# finalSchematics.net
KiCad netlist of a schematic drawn in EAGLE
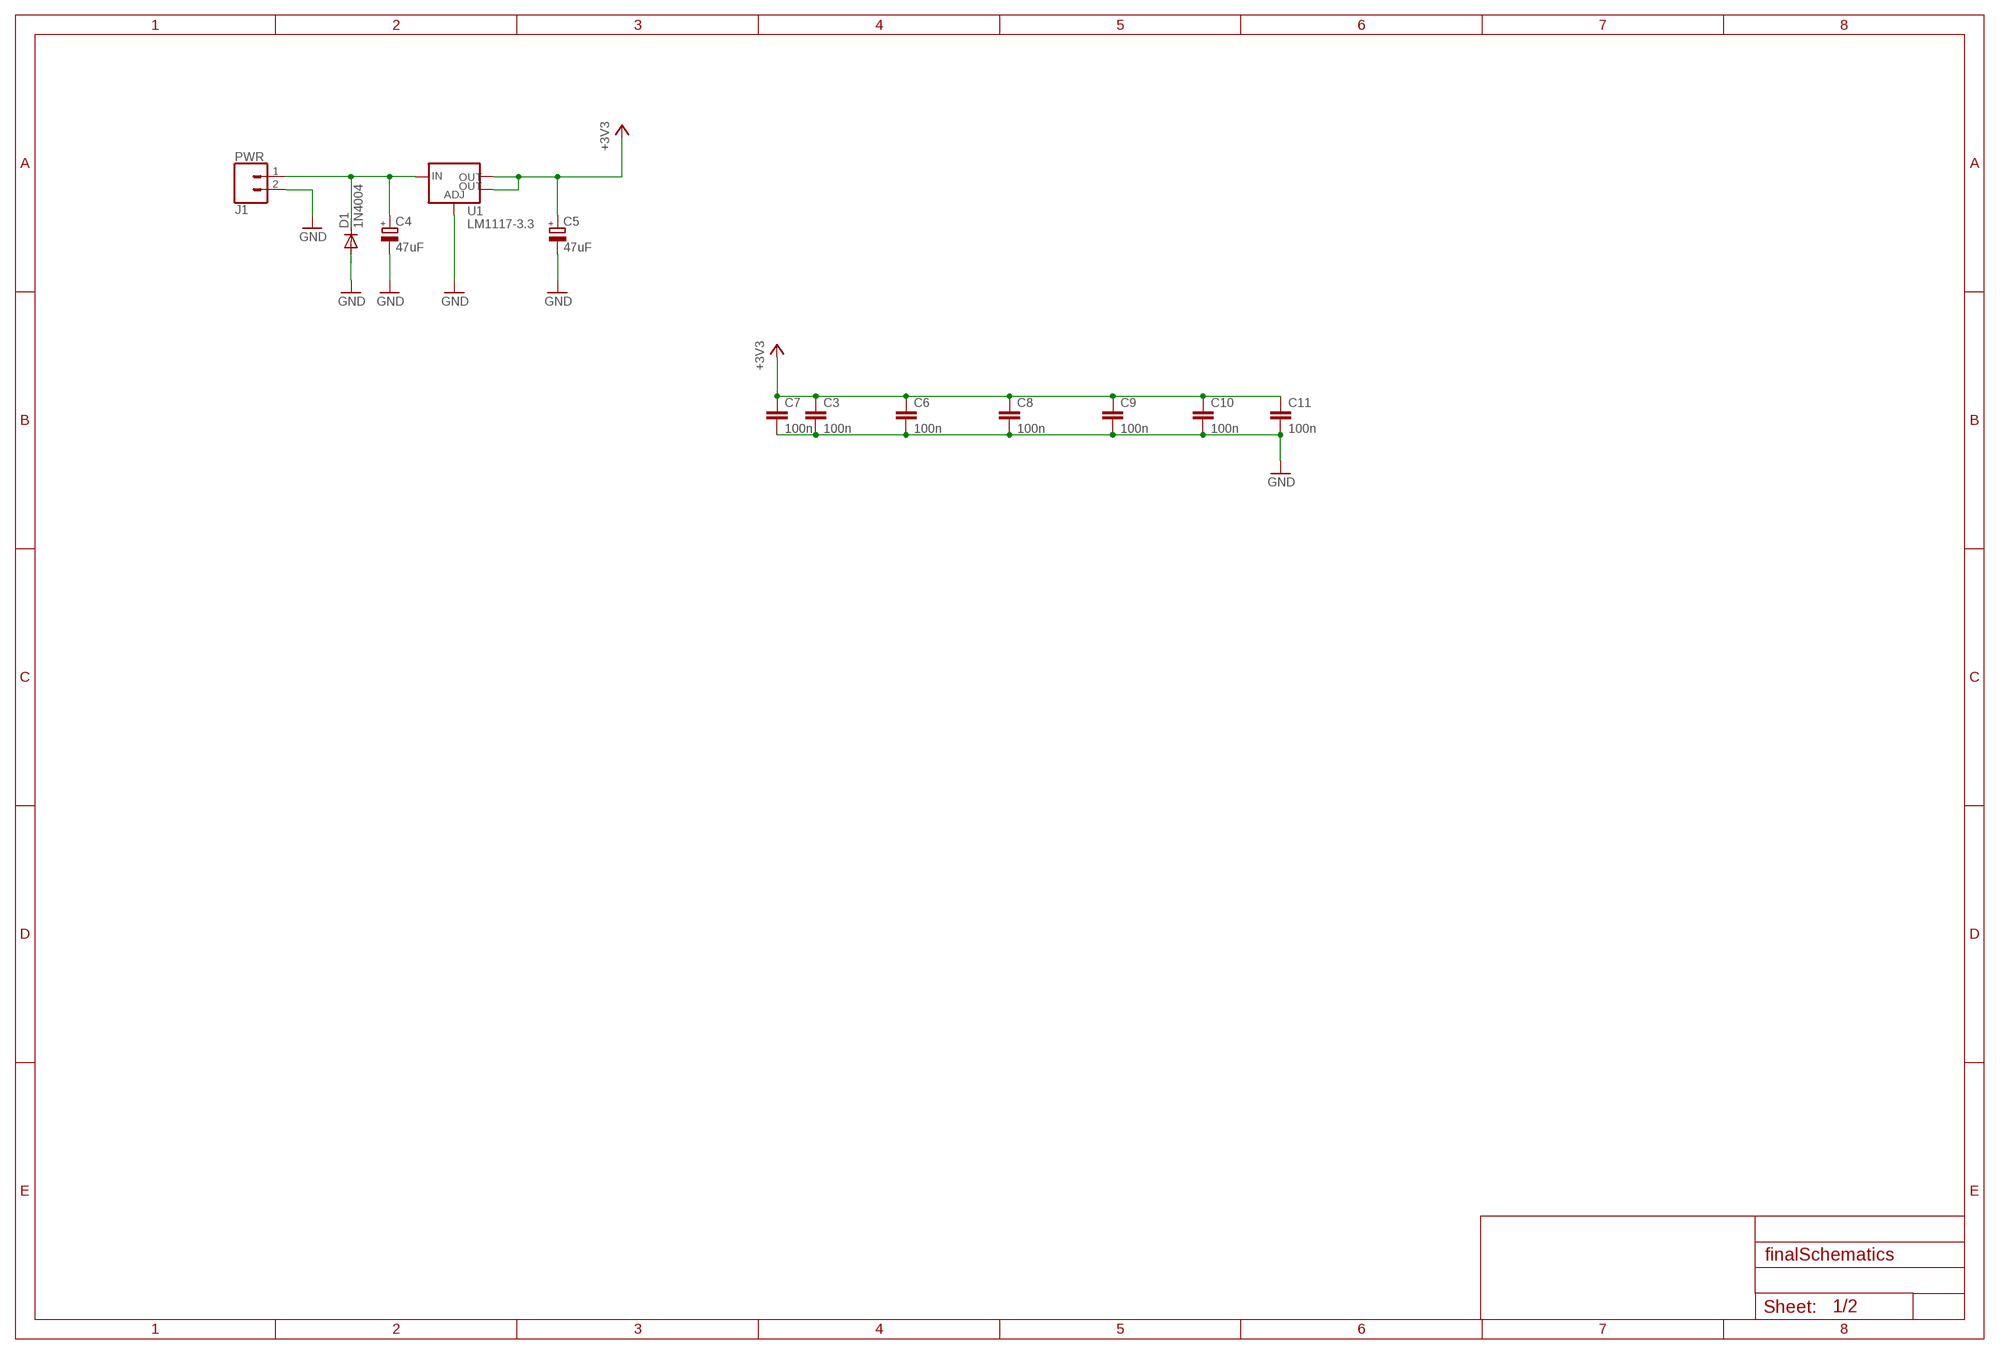
[diagram p0: schematic, sheet 1]
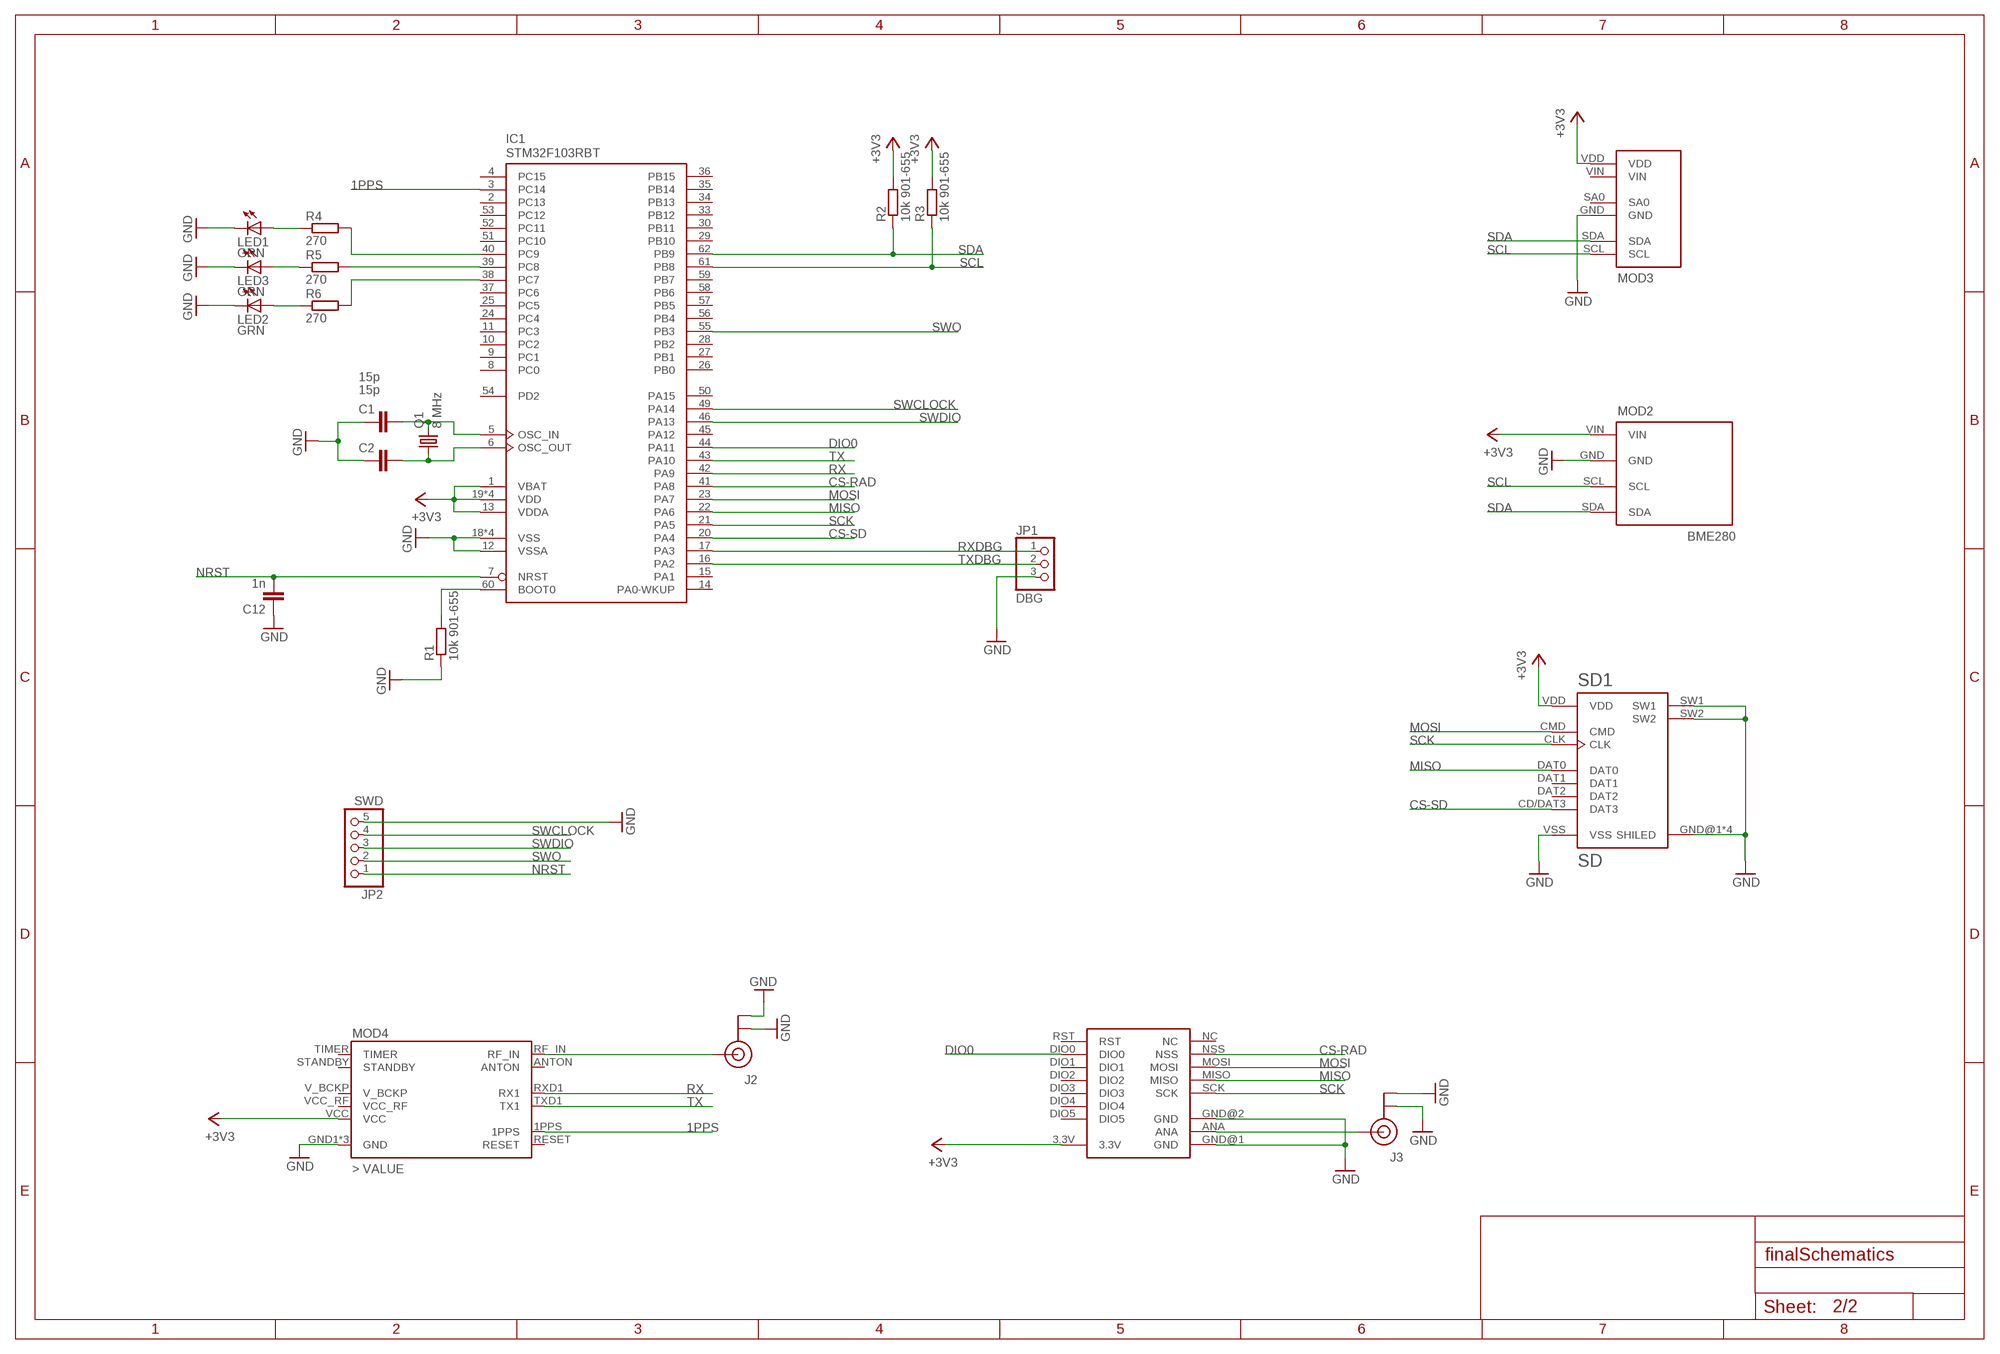
[diagram p1: schematic, sheet 2]

(export (version "E")
  (design (tool "Eeschema 10.0.6"))
  (components
    (comp (ref "C3")
      (value "100n")
      (footprint "eagle-import:C0805")
      (libsource (lib "eagle-import") (part "C-EUC0805"))
    )
    (comp (ref "C4")
      (value "47uF")
      (footprint "eagle-import:153CLV-0810")
      (libsource (lib "eagle-import") (part "CPOL-EU153CLV-0810"))
    )
    (comp (ref "C5")
      (value "47uF")
      (footprint "eagle-import:153CLV-0810")
      (libsource (lib "eagle-import") (part "CPOL-EU153CLV-0810"))
    )
    (comp (ref "C6")
      (value "100n")
      (footprint "eagle-import:C0805")
      (libsource (lib "eagle-import") (part "C-EUC0805"))
    )
    (comp (ref "C7")
      (value "100n")
      (footprint "eagle-import:C0805")
      (libsource (lib "eagle-import") (part "C-EUC0805"))
    )
    (comp (ref "C8")
      (value "100n")
      (footprint "eagle-import:C0805")
      (libsource (lib "eagle-import") (part "C-EUC0805"))
    )
    (comp (ref "C9")
      (value "100n")
      (footprint "eagle-import:C0805")
      (libsource (lib "eagle-import") (part "C-EUC0805"))
    )
    (comp (ref "C10")
      (value "100n")
      (footprint "eagle-import:C0805")
      (libsource (lib "eagle-import") (part "C-EUC0805"))
    )
    (comp (ref "C11")
      (value "100n")
      (footprint "eagle-import:C0805")
      (libsource (lib "eagle-import") (part "C-EUC0805"))
    )
    (comp (ref "D1")
      (value "1N4004")
      (footprint "eagle-import:DO41-10")
      (libsource (lib "eagle-import") (part "1N4004"))
    )
    (comp (ref "J1")
      (value "PWR")
      (footprint "eagle-import:1X02")
      (libsource (lib "eagle-import") (part "CONN_02"))
    )
    (comp (ref "U1")
      (value "LM1117-3.3")
      (footprint "eagle-import:SOT223")
      (libsource (lib "eagle-import") (part "V_REG_LM1117SOT223"))
    )
    (comp (ref "C1")
      (value "15p")
      (footprint "eagle-import:C0805")
      (libsource (lib "eagle-import") (part "C-EUC0805"))
    )
    (comp (ref "C2")
      (value "15p")
      (footprint "eagle-import:C0805")
      (libsource (lib "eagle-import") (part "C-EUC0805"))
    )
    (comp (ref "C12")
      (value "1n")
      (footprint "eagle-import:C0805")
      (libsource (lib "eagle-import") (part "C-EUC0805"))
    )
    (comp (ref "IC1")
      (value "STM32F103RBT")
      (footprint "eagle-import:LQFP64")
      (libsource (lib "eagle-import") (part "STM32F103RTB"))
    )
    (comp (ref "J2")
      (value "U.FL")
      (footprint "eagle-import:U.FL")
      (libsource (lib "eagle-import") (part "U.FL"))
    )
    (comp (ref "J3")
      (value "U.FL")
      (footprint "eagle-import:U.FL")
      (libsource (lib "eagle-import") (part "U.FL"))
    )
    (comp (ref "JP1")
      (value "DBG")
      (footprint "eagle-import:1X03")
      (libsource (lib "eagle-import") (part "PINHD-1X3"))
    )
    (comp (ref "JP2")
      (value "SWD")
      (footprint "eagle-import:1X05")
      (libsource (lib "eagle-import") (part "PINHD-1X5"))
    )
    (comp (ref "LED1")
      (value "GRN")
      (footprint "eagle-import:CHIP-LED0603")
      (libsource (lib "eagle-import") (part "LEDCHIP-LED0603"))
    )
    (comp (ref "LED2")
      (value "GRN")
      (footprint "eagle-import:CHIP-LED0603")
      (libsource (lib "eagle-import") (part "LEDCHIP-LED0603"))
    )
    (comp (ref "LED3")
      (value "GRN")
      (footprint "eagle-import:CHIP-LED0603")
      (libsource (lib "eagle-import") (part "LEDCHIP-LED0603"))
    )
    (comp (ref "MOD2")
      (value "BME280")
      (footprint "eagle-import:BME280")
      (libsource (lib "eagle-import") (part "BME280"))
    )
    (comp (ref "MOD3")
      (value "IMU04A")
      (footprint "eagle-import:IMU04A")
      (libsource (lib "eagle-import") (part "IMU04A"))
    )
    (comp (ref "MOD4")
      (value "GPS")
      (footprint "eagle-import:L70B-GPS")
      (libsource (lib "eagle-import") (part "L70B-GPS"))
    )
    (comp (ref "Q1")
      (value "8 MHz")
      (footprint "eagle-import:HC49UP")
      (libsource (lib "eagle-import") (part "CRYSTALHC49UP"))
    )
    (comp (ref "R1")
      (value "10k 901-655")
      (footprint "eagle-import:R0805")
      (libsource (lib "eagle-import") (part "R-EU_R0805"))
    )
    (comp (ref "R2")
      (value "10k 901-655")
      (footprint "eagle-import:R0805")
      (libsource (lib "eagle-import") (part "R-EU_R0805"))
    )
    (comp (ref "R3")
      (value "10k 901-655")
      (footprint "eagle-import:R0805")
      (libsource (lib "eagle-import") (part "R-EU_R0805"))
    )
    (comp (ref "R4")
      (value "270")
      (footprint "eagle-import:R0805")
      (libsource (lib "eagle-import") (part "resistor_R-EU_R0805"))
    )
    (comp (ref "R5")
      (value "270")
      (footprint "eagle-import:R0805")
      (libsource (lib "eagle-import") (part "resistor_R-EU_R0805"))
    )
    (comp (ref "R6")
      (value "270")
      (footprint "eagle-import:R0805")
      (libsource (lib "eagle-import") (part "resistor_R-EU_R0805"))
    )
    (comp (ref "SD1")
      (value "SD")
      (footprint "eagle-import:MOLEX-SD-104031")
      (libsource (lib "eagle-import") (part "SD"))
    )
    (comp (ref "U$2")
      (value "RFM69")
      (footprint "eagle-import:20X16BOARD")
      (libsource (lib "eagle-import") (part "RFM69"))
    )
  )
  (nets
    (net (code "1") (name "+3V3") (class "Default")
      (node (ref "C10") (pin "1") (pinfunction "1_1") (pintype "passive"))
      (node (ref "C11") (pin "1") (pinfunction "1_1") (pintype "passive"))
      (node (ref "C3") (pin "1") (pinfunction "1_1") (pintype "passive"))
      (node (ref "C5") (pin "+") (pinfunction "+_+") (pintype "passive"))
      (node (ref "C6") (pin "1") (pinfunction "1_1") (pintype "passive"))
      (node (ref "C7") (pin "1") (pinfunction "1_1") (pintype "passive"))
      (node (ref "C8") (pin "1") (pinfunction "1_1") (pintype "passive"))
      (node (ref "C9") (pin "1") (pinfunction "1_1") (pintype "passive"))
      (node (ref "IC1") (pin "1") (pinfunction "VBAT_1") (pintype "power_in"))
      (node (ref "IC1") (pin "13") (pinfunction "VDDA_13") (pintype "power_in"))
      (node (ref "IC1") (pin "19") (pinfunction "VDD_19") (pintype "power_in"))
      (node (ref "IC1") (pin "32") (pinfunction "VDD_32") (pintype "power_in"))
      (node (ref "IC1") (pin "48") (pinfunction "VDD_48") (pintype "power_in"))
      (node (ref "IC1") (pin "64") (pinfunction "VDD_64") (pintype "power_in"))
      (node (ref "MOD2") (pin "VIN") (pinfunction "VIN_VIN") (pintype "bidirectional"))
      (node (ref "MOD3") (pin "VDD") (pinfunction "VDD_VDD") (pintype "bidirectional"))
      (node (ref "MOD4") (pin "VCC") (pinfunction "VCC_VCC") (pintype "power_in"))
      (node (ref "R2") (pin "2") (pinfunction "2_2") (pintype "passive"))
      (node (ref "R3") (pin "2") (pinfunction "2_2") (pintype "passive"))
      (node (ref "SD1") (pin "VDD") (pinfunction "VDD_VDD") (pintype "power_in"))
      (node (ref "U$2") (pin "3.3V") (pinfunction "3.3V_3.3V") (pintype "power_in"))
      (node (ref "U1") (pin "2") (pinfunction "OUT_2") (pintype "output"))
      (node (ref "U1") (pin "4") (pinfunction "OUT_4") (pintype "output"))
    )
    (net (code "2") (name "1PPS") (class "Default")
      (node (ref "IC1") (pin "3") (pinfunction "PC14_3") (pintype "bidirectional"))
      (node (ref "MOD4") (pin "1PPS") (pinfunction "1PPS_1PPS") (pintype "output"))
    )
    (net (code "3") (name "CS-RAD") (class "Default")
      (node (ref "IC1") (pin "41") (pinfunction "PA8_41") (pintype "bidirectional"))
      (node (ref "U$2") (pin "NSS") (pinfunction "NSS_NSS") (pintype "bidirectional"))
    )
    (net (code "4") (name "CS-SD") (class "Default")
      (node (ref "IC1") (pin "20") (pinfunction "PA4_20") (pintype "bidirectional"))
      (node (ref "SD1") (pin "CD/DAT3") (pinfunction "DAT3_CD/DAT3") (pintype "bidirectional"))
    )
    (net (code "5") (name "DIO0") (class "Default")
      (node (ref "IC1") (pin "44") (pinfunction "PA11_44") (pintype "bidirectional"))
      (node (ref "U$2") (pin "DIO0") (pinfunction "DIO0_DIO0") (pintype "bidirectional"))
    )
    (net (code "6") (name "GND") (class "Default")
      (node (ref "C1") (pin "1") (pinfunction "1_1") (pintype "passive"))
      (node (ref "C10") (pin "2") (pinfunction "2_2") (pintype "passive"))
      (node (ref "C11") (pin "2") (pinfunction "2_2") (pintype "passive"))
      (node (ref "C12") (pin "1") (pinfunction "1_1") (pintype "passive"))
      (node (ref "C2") (pin "1") (pinfunction "1_1") (pintype "passive"))
      (node (ref "C3") (pin "2") (pinfunction "2_2") (pintype "passive"))
      (node (ref "C4") (pin "-") (pinfunction "-_-") (pintype "passive"))
      (node (ref "C5") (pin "-") (pinfunction "-_-") (pintype "passive"))
      (node (ref "C6") (pin "2") (pinfunction "2_2") (pintype "passive"))
      (node (ref "C7") (pin "2") (pinfunction "2_2") (pintype "passive"))
      (node (ref "C8") (pin "2") (pinfunction "2_2") (pintype "passive"))
      (node (ref "C9") (pin "2") (pinfunction "2_2") (pintype "passive"))
      (node (ref "D1") (pin "A") (pinfunction "A_A") (pintype "passive"))
      (node (ref "IC1") (pin "12") (pinfunction "VSSA_12") (pintype "power_in"))
      (node (ref "IC1") (pin "18") (pinfunction "VSS_18") (pintype "power_in"))
      (node (ref "IC1") (pin "31") (pinfunction "VSS_31") (pintype "power_in"))
      (node (ref "IC1") (pin "47") (pinfunction "VSS_47") (pintype "power_in"))
      (node (ref "IC1") (pin "63") (pinfunction "VSS_63") (pintype "power_in"))
      (node (ref "J1") (pin "2") (pinfunction "2_2") (pintype "passive"))
      (node (ref "J2") (pin "P$1") (pinfunction "GND_P$1") (pintype "bidirectional"))
      (node (ref "J2") (pin "P$2") (pinfunction "GND_P$2") (pintype "bidirectional"))
      (node (ref "J3") (pin "P$1") (pinfunction "GND_P$1") (pintype "bidirectional"))
      (node (ref "J3") (pin "P$2") (pinfunction "GND_P$2") (pintype "bidirectional"))
      (node (ref "JP1") (pin "3") (pinfunction "3_3") (pintype "passive"))
      (node (ref "JP2") (pin "5") (pinfunction "5_5") (pintype "passive"))
      (node (ref "LED1") (pin "C") (pinfunction "C_C") (pintype "passive"))
      (node (ref "LED2") (pin "C") (pinfunction "C_C") (pintype "passive"))
      (node (ref "LED3") (pin "C") (pinfunction "C_C") (pintype "passive"))
      (node (ref "MOD2") (pin "GND") (pinfunction "GND_GND") (pintype "bidirectional"))
      (node (ref "MOD3") (pin "GND") (pinfunction "GND_GND") (pintype "bidirectional"))
      (node (ref "MOD4") (pin "GND1") (pinfunction "GND_GND1") (pintype "power_in"))
      (node (ref "MOD4") (pin "GND2") (pinfunction "GND_GND2") (pintype "power_in"))
      (node (ref "MOD4") (pin "GND3") (pinfunction "GND_GND3") (pintype "power_in"))
      (node (ref "R1") (pin "1") (pinfunction "1_1") (pintype "passive"))
      (node (ref "SD1") (pin "GND@1") (pinfunction "SHILED_GND@1") (pintype "bidirectional"))
      (node (ref "SD1") (pin "GND@2") (pinfunction "SHILED_GND@2") (pintype "bidirectional"))
      (node (ref "SD1") (pin "GND@3") (pinfunction "SHILED_GND@3") (pintype "bidirectional"))
      (node (ref "SD1") (pin "GND@4") (pinfunction "SHILED_GND@4") (pintype "bidirectional"))
      (node (ref "SD1") (pin "SW1") (pinfunction "SW1_SW1") (pintype "bidirectional"))
      (node (ref "SD1") (pin "SW2") (pinfunction "SW2_SW2") (pintype "bidirectional"))
      (node (ref "SD1") (pin "VSS") (pinfunction "VSS_VSS") (pintype "passive"))
      (node (ref "U$2") (pin "GND@1") (pinfunction "GND_GND@1") (pintype "power_in"))
      (node (ref "U$2") (pin "GND@2") (pinfunction "GND_GND@2") (pintype "power_in"))
      (node (ref "U1") (pin "1") (pinfunction "ADJ_1") (pintype "input"))
    )
    (net (code "7") (name "MISO") (class "Default")
      (node (ref "IC1") (pin "22") (pinfunction "PA6_22") (pintype "bidirectional"))
      (node (ref "SD1") (pin "DAT0") (pinfunction "DAT0_DAT0") (pintype "bidirectional"))
      (node (ref "U$2") (pin "MISO") (pinfunction "MISO_MISO") (pintype "bidirectional"))
    )
    (net (code "8") (name "MOSI") (class "Default")
      (node (ref "IC1") (pin "23") (pinfunction "PA7_23") (pintype "bidirectional"))
      (node (ref "SD1") (pin "CMD") (pinfunction "CMD_CMD") (pintype "input"))
      (node (ref "U$2") (pin "MOSI") (pinfunction "MOSI_MOSI") (pintype "bidirectional"))
    )
    (net (code "9") (name "NC") (class "Default")
      (node (ref "U$2") (pin "NC") (pinfunction "NC_NC") (pintype "power_in"))
    )
    (net (code "10") (name "NRST") (class "Default")
      (node (ref "C12") (pin "2") (pinfunction "2_2") (pintype "passive"))
      (node (ref "IC1") (pin "7") (pinfunction "NRST_7") (pintype "bidirectional"))
      (node (ref "JP2") (pin "1") (pinfunction "1_1") (pintype "passive"))
    )
    (net (code "11") (name "Net-(IC1-BOOT0)") (class "Default")
      (node (ref "IC1") (pin "60") (pinfunction "BOOT0_60") (pintype "input"))
      (node (ref "R1") (pin "2") (pinfunction "2_2") (pintype "passive"))
    )
    (net (code "12") (name "Net-(IC1-OSC_IN)") (class "Default")
      (node (ref "C1") (pin "2") (pinfunction "2_2") (pintype "passive"))
      (node (ref "IC1") (pin "5") (pinfunction "OSC_IN_5") (pintype "bidirectional"))
      (node (ref "Q1") (pin "2") (pinfunction "2_2") (pintype "passive"))
    )
    (net (code "13") (name "Net-(IC1-OSC_OUT)") (class "Default")
      (node (ref "C2") (pin "2") (pinfunction "2_2") (pintype "passive"))
      (node (ref "IC1") (pin "6") (pinfunction "OSC_OUT_6") (pintype "bidirectional"))
      (node (ref "Q1") (pin "1") (pinfunction "1_1") (pintype "passive"))
    )
    (net (code "14") (name "Net-(IC1-PC7)") (class "Default")
      (node (ref "IC1") (pin "38") (pinfunction "PC7_38") (pintype "bidirectional"))
      (node (ref "R6") (pin "2") (pinfunction "2_2") (pintype "passive"))
    )
    (net (code "15") (name "Net-(IC1-PC8)") (class "Default")
      (node (ref "IC1") (pin "39") (pinfunction "PC8_39") (pintype "bidirectional"))
      (node (ref "R5") (pin "2") (pinfunction "2_2") (pintype "passive"))
    )
    (net (code "16") (name "Net-(IC1-PC9)") (class "Default")
      (node (ref "IC1") (pin "40") (pinfunction "PC9_40") (pintype "bidirectional"))
      (node (ref "R4") (pin "2") (pinfunction "2_2") (pintype "passive"))
    )
    (net (code "17") (name "Net-(J2-SIGNAL)") (class "Default")
      (node (ref "J2") (pin "P$3") (pinfunction "SIGNAL_P$3") (pintype "bidirectional"))
      (node (ref "MOD4") (pin "RF_IN") (pinfunction "RF_IN_RF_IN") (pintype "output"))
    )
    (net (code "18") (name "Net-(J3-SIGNAL)") (class "Default")
      (node (ref "J3") (pin "P$3") (pinfunction "SIGNAL_P$3") (pintype "bidirectional"))
      (node (ref "U$2") (pin "ANA") (pinfunction "ANA_ANA") (pintype "bidirectional"))
    )
    (net (code "19") (name "Net-(LED1-PadA)") (class "Default")
      (node (ref "LED1") (pin "A") (pinfunction "A_A") (pintype "passive"))
      (node (ref "R4") (pin "1") (pinfunction "1_1") (pintype "passive"))
    )
    (net (code "20") (name "Net-(LED2-PadA)") (class "Default")
      (node (ref "LED2") (pin "A") (pinfunction "A_A") (pintype "passive"))
      (node (ref "R6") (pin "1") (pinfunction "1_1") (pintype "passive"))
    )
    (net (code "21") (name "Net-(LED3-PadA)") (class "Default")
      (node (ref "LED3") (pin "A") (pinfunction "A_A") (pintype "passive"))
      (node (ref "R5") (pin "1") (pinfunction "1_1") (pintype "passive"))
    )
    (net (code "22") (name "Net-(U1-IN)") (class "Default")
      (node (ref "C4") (pin "+") (pinfunction "+_+") (pintype "passive"))
      (node (ref "D1") (pin "C") (pinfunction "C_C") (pintype "passive"))
      (node (ref "J1") (pin "1") (pinfunction "1_1") (pintype "passive"))
      (node (ref "U1") (pin "3") (pinfunction "IN_3") (pintype "input"))
    )
    (net (code "23") (name "RX") (class "Default")
      (node (ref "IC1") (pin "42") (pinfunction "PA9_42") (pintype "bidirectional"))
      (node (ref "MOD4") (pin "RXD1") (pinfunction "RX1_RXD1") (pintype "output"))
    )
    (net (code "24") (name "RXDBG") (class "Default")
      (node (ref "IC1") (pin "17") (pinfunction "PA3_17") (pintype "bidirectional"))
      (node (ref "JP1") (pin "1") (pinfunction "1_1") (pintype "passive"))
    )
    (net (code "25") (name "SCK") (class "Default")
      (node (ref "IC1") (pin "21") (pinfunction "PA5_21") (pintype "bidirectional"))
      (node (ref "SD1") (pin "CLK") (pinfunction "CLK_CLK") (pintype "input"))
      (node (ref "U$2") (pin "SCK") (pinfunction "SCK_SCK") (pintype "bidirectional"))
    )
    (net (code "26") (name "SCL") (class "Default")
      (node (ref "IC1") (pin "61") (pinfunction "PB8_61") (pintype "bidirectional"))
      (node (ref "MOD2") (pin "SCL") (pinfunction "SCL_SCL") (pintype "bidirectional"))
      (node (ref "MOD3") (pin "SCL") (pinfunction "SCL_SCL") (pintype "bidirectional"))
      (node (ref "R3") (pin "1") (pinfunction "1_1") (pintype "passive"))
    )
    (net (code "27") (name "SDA") (class "Default")
      (node (ref "IC1") (pin "62") (pinfunction "PB9_62") (pintype "bidirectional"))
      (node (ref "MOD2") (pin "SDA") (pinfunction "SDA_SDA") (pintype "bidirectional"))
      (node (ref "MOD3") (pin "SDA") (pinfunction "SDA_SDA") (pintype "bidirectional"))
      (node (ref "R2") (pin "1") (pinfunction "1_1") (pintype "passive"))
    )
    (net (code "28") (name "SWCLOCK") (class "Default")
      (node (ref "IC1") (pin "49") (pinfunction "PA14_49") (pintype "bidirectional"))
      (node (ref "JP2") (pin "4") (pinfunction "4_4") (pintype "passive"))
    )
    (net (code "29") (name "SWDIO") (class "Default")
      (node (ref "IC1") (pin "46") (pinfunction "PA13_46") (pintype "bidirectional"))
      (node (ref "JP2") (pin "3") (pinfunction "3_3") (pintype "passive"))
    )
    (net (code "30") (name "SWO") (class "Default")
      (node (ref "IC1") (pin "55") (pinfunction "PB3_55") (pintype "bidirectional"))
      (node (ref "JP2") (pin "2") (pinfunction "2_2") (pintype "passive"))
    )
    (net (code "31") (name "TX") (class "Default")
      (node (ref "IC1") (pin "43") (pinfunction "PA10_43") (pintype "bidirectional"))
      (node (ref "MOD4") (pin "TXD1") (pinfunction "TX1_TXD1") (pintype "input"))
    )
    (net (code "32") (name "TXDBG") (class "Default")
      (node (ref "IC1") (pin "16") (pinfunction "PA2_16") (pintype "bidirectional"))
      (node (ref "JP1") (pin "2") (pinfunction "2_2") (pintype "passive"))
    )
    (net (code "33") (name "unconnected-(IC1-PA0-WKUP-Pad14)") (class "Default")
      (node (ref "IC1") (pin "14") (pinfunction "PA0-WKUP_14") (pintype "bidirectional"))
    )
    (net (code "34") (name "unconnected-(IC1-PA1-Pad15)") (class "Default")
      (node (ref "IC1") (pin "15") (pinfunction "PA1_15") (pintype "bidirectional"))
    )
    (net (code "35") (name "unconnected-(IC1-PA12-Pad45)") (class "Default")
      (node (ref "IC1") (pin "45") (pinfunction "PA12_45") (pintype "bidirectional"))
    )
    (net (code "36") (name "unconnected-(IC1-PA15-Pad50)") (class "Default")
      (node (ref "IC1") (pin "50") (pinfunction "PA15_50") (pintype "bidirectional"))
    )
    (net (code "37") (name "unconnected-(IC1-PB0-Pad26)") (class "Default")
      (node (ref "IC1") (pin "26") (pinfunction "PB0_26") (pintype "bidirectional"))
    )
    (net (code "38") (name "unconnected-(IC1-PB1-Pad27)") (class "Default")
      (node (ref "IC1") (pin "27") (pinfunction "PB1_27") (pintype "bidirectional"))
    )
    (net (code "39") (name "unconnected-(IC1-PB2-Pad28)") (class "Default")
      (node (ref "IC1") (pin "28") (pinfunction "PB2_28") (pintype "bidirectional"))
    )
    (net (code "40") (name "unconnected-(IC1-PB4-Pad56)") (class "Default")
      (node (ref "IC1") (pin "56") (pinfunction "PB4_56") (pintype "bidirectional"))
    )
    (net (code "41") (name "unconnected-(IC1-PB5-Pad57)") (class "Default")
      (node (ref "IC1") (pin "57") (pinfunction "PB5_57") (pintype "bidirectional"))
    )
    (net (code "42") (name "unconnected-(IC1-PB6-Pad58)") (class "Default")
      (node (ref "IC1") (pin "58") (pinfunction "PB6_58") (pintype "bidirectional"))
    )
    (net (code "43") (name "unconnected-(IC1-PB7-Pad59)") (class "Default")
      (node (ref "IC1") (pin "59") (pinfunction "PB7_59") (pintype "bidirectional"))
    )
    (net (code "44") (name "unconnected-(IC1-PB10-Pad29)") (class "Default")
      (node (ref "IC1") (pin "29") (pinfunction "PB10_29") (pintype "bidirectional"))
    )
    (net (code "45") (name "unconnected-(IC1-PB11-Pad30)") (class "Default")
      (node (ref "IC1") (pin "30") (pinfunction "PB11_30") (pintype "bidirectional"))
    )
    (net (code "46") (name "unconnected-(IC1-PB12-Pad33)") (class "Default")
      (node (ref "IC1") (pin "33") (pinfunction "PB12_33") (pintype "bidirectional"))
    )
    (net (code "47") (name "unconnected-(IC1-PB13-Pad34)") (class "Default")
      (node (ref "IC1") (pin "34") (pinfunction "PB13_34") (pintype "bidirectional"))
    )
    (net (code "48") (name "unconnected-(IC1-PB14-Pad35)") (class "Default")
      (node (ref "IC1") (pin "35") (pinfunction "PB14_35") (pintype "bidirectional"))
    )
    (net (code "49") (name "unconnected-(IC1-PB15-Pad36)") (class "Default")
      (node (ref "IC1") (pin "36") (pinfunction "PB15_36") (pintype "bidirectional"))
    )
    (net (code "50") (name "unconnected-(IC1-PC0-Pad8)") (class "Default")
      (node (ref "IC1") (pin "8") (pinfunction "PC0_8") (pintype "bidirectional"))
    )
    (net (code "51") (name "unconnected-(IC1-PC1-Pad9)") (class "Default")
      (node (ref "IC1") (pin "9") (pinfunction "PC1_9") (pintype "bidirectional"))
    )
    (net (code "52") (name "unconnected-(IC1-PC2-Pad10)") (class "Default")
      (node (ref "IC1") (pin "10") (pinfunction "PC2_10") (pintype "bidirectional"))
    )
    (net (code "53") (name "unconnected-(IC1-PC3-Pad11)") (class "Default")
      (node (ref "IC1") (pin "11") (pinfunction "PC3_11") (pintype "bidirectional"))
    )
    (net (code "54") (name "unconnected-(IC1-PC4-Pad24)") (class "Default")
      (node (ref "IC1") (pin "24") (pinfunction "PC4_24") (pintype "bidirectional"))
    )
    (net (code "55") (name "unconnected-(IC1-PC5-Pad25)") (class "Default")
      (node (ref "IC1") (pin "25") (pinfunction "PC5_25") (pintype "bidirectional"))
    )
    (net (code "56") (name "unconnected-(IC1-PC6-Pad37)") (class "Default")
      (node (ref "IC1") (pin "37") (pinfunction "PC6_37") (pintype "bidirectional"))
    )
    (net (code "57") (name "unconnected-(IC1-PC10-Pad51)") (class "Default")
      (node (ref "IC1") (pin "51") (pinfunction "PC10_51") (pintype "bidirectional"))
    )
    (net (code "58") (name "unconnected-(IC1-PC11-Pad52)") (class "Default")
      (node (ref "IC1") (pin "52") (pinfunction "PC11_52") (pintype "bidirectional"))
    )
    (net (code "59") (name "unconnected-(IC1-PC12-Pad53)") (class "Default")
      (node (ref "IC1") (pin "53") (pinfunction "PC12_53") (pintype "bidirectional"))
    )
    (net (code "60") (name "unconnected-(IC1-PC13-Pad2)") (class "Default")
      (node (ref "IC1") (pin "2") (pinfunction "PC13_2") (pintype "bidirectional"))
    )
    (net (code "61") (name "unconnected-(IC1-PC15-Pad4)") (class "Default")
      (node (ref "IC1") (pin "4") (pinfunction "PC15_4") (pintype "bidirectional"))
    )
    (net (code "62") (name "unconnected-(IC1-PD2-Pad54)") (class "Default")
      (node (ref "IC1") (pin "54") (pinfunction "PD2_54") (pintype "bidirectional"))
    )
    (net (code "63") (name "unconnected-(MOD3-PadSA0)") (class "Default")
      (node (ref "MOD3") (pin "SA0") (pinfunction "SA0_SA0") (pintype "bidirectional"))
    )
    (net (code "64") (name "unconnected-(MOD3-PadVIN)") (class "Default")
      (node (ref "MOD3") (pin "VIN") (pinfunction "VIN_VIN") (pintype "bidirectional"))
    )
    (net (code "65") (name "unconnected-(MOD4-PadANTON)") (class "Default")
      (node (ref "MOD4") (pin "ANTON") (pinfunction "ANTON_ANTON") (pintype "input"))
    )
    (net (code "66") (name "unconnected-(MOD4-PadRESET)") (class "Default")
      (node (ref "MOD4") (pin "RESET") (pinfunction "RESET_RESET") (pintype "bidirectional"))
    )
    (net (code "67") (name "unconnected-(MOD4-PadSTANDBY)") (class "Default")
      (node (ref "MOD4") (pin "STANDBY") (pinfunction "STANDBY_STANDBY") (pintype "input"))
    )
    (net (code "68") (name "unconnected-(MOD4-PadTIMER)") (class "Default")
      (node (ref "MOD4") (pin "TIMER") (pinfunction "TIMER_TIMER") (pintype "input"))
    )
    (net (code "69") (name "unconnected-(MOD4-PadVCC_RF)") (class "Default")
      (node (ref "MOD4") (pin "VCC_RF") (pinfunction "VCC_RF_VCC_RF") (pintype "bidirectional"))
    )
    (net (code "70") (name "unconnected-(MOD4-PadV_BCKP)") (class "Default")
      (node (ref "MOD4") (pin "V_BCKP") (pinfunction "V_BCKP_V_BCKP") (pintype "bidirectional"))
    )
    (net (code "71") (name "unconnected-(SD1-PadDAT1)") (class "Default")
      (node (ref "SD1") (pin "DAT1") (pinfunction "DAT1_DAT1") (pintype "bidirectional"))
    )
    (net (code "72") (name "unconnected-(SD1-PadDAT2)") (class "Default")
      (node (ref "SD1") (pin "DAT2") (pinfunction "DAT2_DAT2") (pintype "bidirectional"))
    )
    (net (code "73") (name "unconnected-(U$2-PadDIO1)") (class "Default")
      (node (ref "U$2") (pin "DIO1") (pinfunction "DIO1_DIO1") (pintype "bidirectional"))
    )
    (net (code "74") (name "unconnected-(U$2-PadDIO2)") (class "Default")
      (node (ref "U$2") (pin "DIO2") (pinfunction "DIO2_DIO2") (pintype "bidirectional"))
    )
    (net (code "75") (name "unconnected-(U$2-PadDIO3)") (class "Default")
      (node (ref "U$2") (pin "DIO3") (pinfunction "DIO3_DIO3") (pintype "bidirectional"))
    )
    (net (code "76") (name "unconnected-(U$2-PadDIO4)") (class "Default")
      (node (ref "U$2") (pin "DIO4") (pinfunction "DIO4_DIO4") (pintype "bidirectional"))
    )
    (net (code "77") (name "unconnected-(U$2-PadDIO5)") (class "Default")
      (node (ref "U$2") (pin "DIO5") (pinfunction "DIO5_DIO5") (pintype "bidirectional"))
    )
    (net (code "78") (name "unconnected-(U$2-PadRST)") (class "Default")
      (node (ref "U$2") (pin "RST") (pinfunction "RST_RST") (pintype "bidirectional"))
    )
  )
)
